# driverv7.net
KiCad netlist of a schematic drawn in Altium Designer
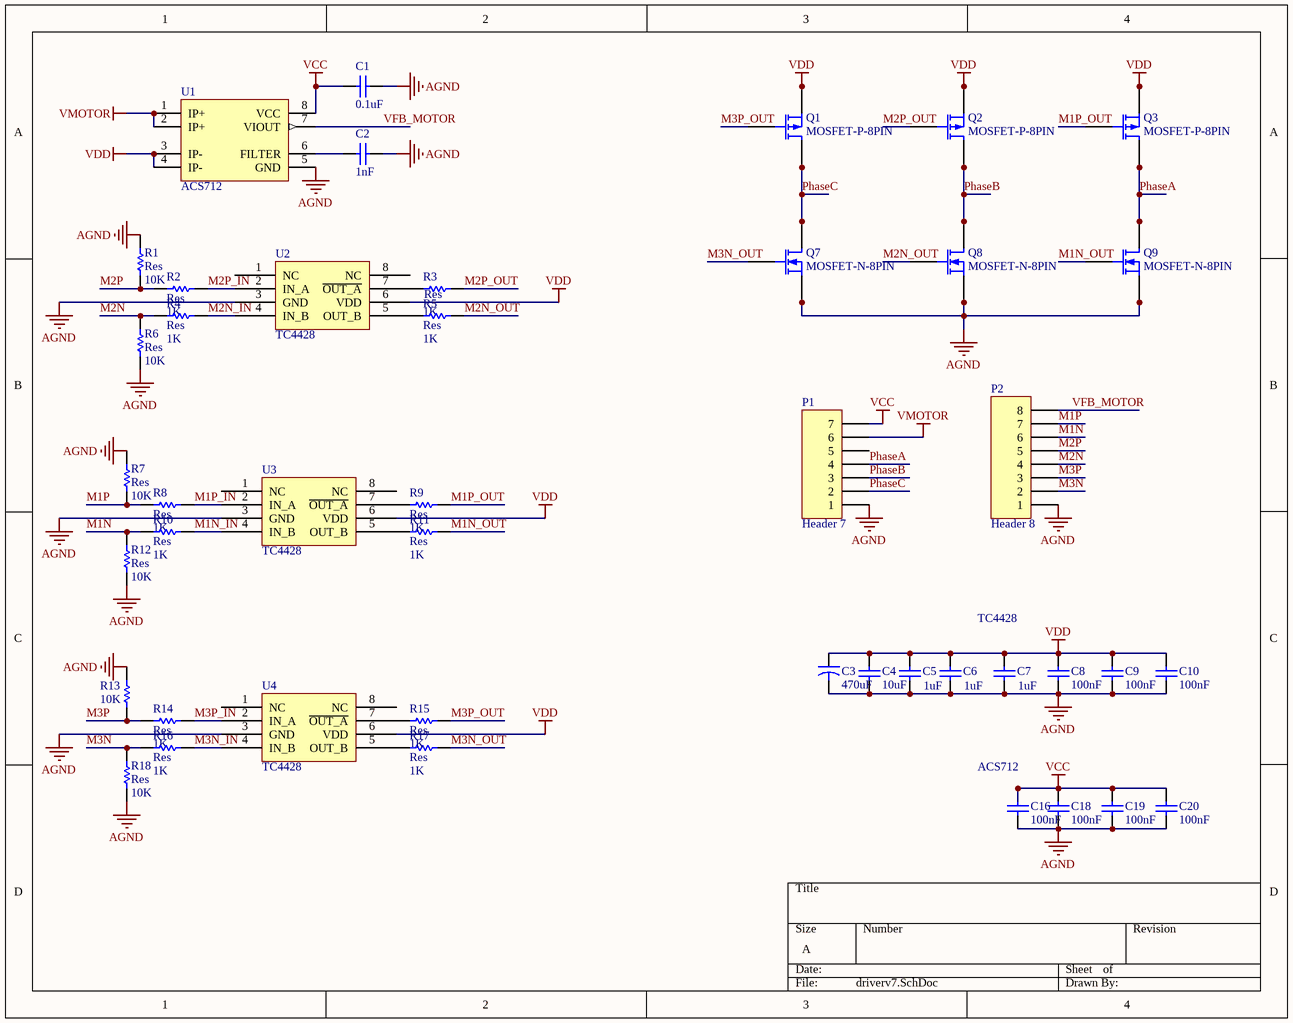
[diagram p0: driverv7.SchDoc]

(export (version "E")
  (design (tool "Eeschema 10.0.6"))
  (components
    (comp (ref "C1")
      (value "0.1uF")
      (footprint "2012[0805]")
      (description "Capacitor")
      (fields (field (name "Comment") "Cap_UP") (field (name "PUBLISHER") "Altium Limited"))
      (libsource (lib "KN2CLib") (part "Cap_UP"))
    )
    (comp (ref "C2")
      (value "1nF")
      (footprint "2012[0805]")
      (description "Capacitor")
      (fields (field (name "Comment") "Cap_UP") (field (name "PUBLISHER") "Altium Limited"))
      (libsource (lib "KN2CLib") (part "Cap_UP"))
    )
    (comp (ref "C3")
      (value "470uF")
      (footprint "7343")
      (description "Capacitor")
      (fields (field (name "Comment") "Cap_El_200V") (field (name "PUBLISHER") "Altium Limited"))
      (libsource (lib "KN2CLib") (part "Cap_El_200V"))
    )
    (comp (ref "C4")
      (value "10uF")
      (footprint "2012[0805]")
      (description "Capacitor")
      (fields (field (name "Comment") "Cap_UP") (field (name "PUBLISHER") "Altium Limited"))
      (libsource (lib "KN2CLib") (part "Cap_UP"))
    )
    (comp (ref "C5")
      (value "1uF")
      (footprint "2012[0805]")
      (description "Capacitor")
      (fields (field (name "Comment") "Cap_UP") (field (name "PUBLISHER") "Altium Limited"))
      (libsource (lib "KN2CLib") (part "Cap_UP"))
    )
    (comp (ref "C6")
      (value "1uF")
      (footprint "2012[0805]")
      (description "Capacitor")
      (fields (field (name "Comment") "Cap_UP") (field (name "PUBLISHER") "Altium Limited"))
      (libsource (lib "KN2CLib") (part "Cap_UP"))
    )
    (comp (ref "C7")
      (value "1uF")
      (footprint "2012[0805]")
      (description "Capacitor")
      (fields (field (name "Comment") "Cap_UP") (field (name "PUBLISHER") "Altium Limited"))
      (libsource (lib "KN2CLib") (part "Cap_UP"))
    )
    (comp (ref "C8")
      (value "100nF")
      (footprint "2012[0805]")
      (description "Capacitor")
      (fields (field (name "Comment") "Cap_UP") (field (name "PUBLISHER") "Altium Limited"))
      (libsource (lib "KN2CLib") (part "Cap_UP"))
    )
    (comp (ref "C9")
      (value "100nF")
      (footprint "2012[0805]")
      (description "Capacitor")
      (fields (field (name "Comment") "Cap_UP") (field (name "PUBLISHER") "Altium Limited"))
      (libsource (lib "KN2CLib") (part "Cap_UP"))
    )
    (comp (ref "C10")
      (value "100nF")
      (footprint "2012[0805]")
      (description "Capacitor")
      (fields (field (name "Comment") "Cap_UP") (field (name "PUBLISHER") "Altium Limited"))
      (libsource (lib "KN2CLib") (part "Cap_UP"))
    )
    (comp (ref "C16")
      (value "100nF")
      (footprint "2012[0805]")
      (description "Capacitor")
      (fields (field (name "Comment") "Cap_UP") (field (name "PUBLISHER") "Altium Limited"))
      (libsource (lib "KN2CLib") (part "Cap_UP"))
    )
    (comp (ref "C18")
      (value "100nF")
      (footprint "2012[0805]")
      (description "Capacitor")
      (fields (field (name "Comment") "Cap_UP") (field (name "PUBLISHER") "Altium Limited"))
      (libsource (lib "KN2CLib") (part "Cap_UP"))
    )
    (comp (ref "C19")
      (value "100nF")
      (footprint "2012[0805]")
      (description "Capacitor")
      (fields (field (name "Comment") "Cap_UP") (field (name "PUBLISHER") "Altium Limited"))
      (libsource (lib "KN2CLib") (part "Cap_UP"))
    )
    (comp (ref "C20")
      (value "100nF")
      (footprint "2012[0805]")
      (description "Capacitor")
      (fields (field (name "Comment") "Cap_UP") (field (name "PUBLISHER") "Altium Limited"))
      (libsource (lib "KN2CLib") (part "Cap_UP"))
    )
    (comp (ref "P1")
      (value "Header 7")
      (footprint "HDR1X7")
      (description "Header, 7-Pin")
      (fields (field (name "PUBLISHER") "Altium Limited"))
      (libsource (lib "Miscellaneous Connectors") (part "Header 7"))
    )
    (comp (ref "P2")
      (value "Header 8")
      (footprint "HDR1X8")
      (description "Header, 8-Pin")
      (fields (field (name "PUBLISHER") "Altium Limited"))
      (libsource (lib "Miscellaneous Connectors") (part "Header 8"))
    )
    (comp (ref "Q1")
      (value "MOSFET-P-8PIN")
      (footprint "SO-8_N")
      (description "P-Channel MOSFET")
      (fields (field (name "PUBLISHER") "Altium Limited"))
      (libsource (lib "KN2CLib") (part "MOSFET-P-8PIN"))
    )
    (comp (ref "Q2")
      (value "MOSFET-P-8PIN")
      (footprint "SO-8_N")
      (description "P-Channel MOSFET")
      (fields (field (name "PUBLISHER") "Altium Limited"))
      (libsource (lib "KN2CLib") (part "MOSFET-P-8PIN"))
    )
    (comp (ref "Q3")
      (value "MOSFET-P-8PIN")
      (footprint "SO-8_N")
      (description "P-Channel MOSFET")
      (fields (field (name "PUBLISHER") "Altium Limited"))
      (libsource (lib "KN2CLib") (part "MOSFET-P-8PIN"))
    )
    (comp (ref "Q7")
      (value "MOSFET-N-8PIN")
      (footprint "SO-8_N")
      (description "N-Channel MOSFET")
      (fields (field (name "PUBLISHER") "Altium Limited"))
      (libsource (lib "KN2CLib") (part "MOSFET-N-8PIN"))
    )
    (comp (ref "Q8")
      (value "MOSFET-N-8PIN")
      (footprint "SO-8_N")
      (description "N-Channel MOSFET")
      (fields (field (name "PUBLISHER") "Altium Limited"))
      (libsource (lib "KN2CLib") (part "MOSFET-N-8PIN"))
    )
    (comp (ref "Q9")
      (value "MOSFET-N-8PIN")
      (footprint "SO-8_N")
      (description "N-Channel MOSFET")
      (fields (field (name "PUBLISHER") "Altium Limited"))
      (libsource (lib "KN2CLib") (part "MOSFET-N-8PIN"))
    )
    (comp (ref "R1")
      (value "Res")
      (footprint "2012[0805]")
      (description "Semiconductor Resistor")
      (fields (field (name "ALTIUM_VALUE") "10K") (field (name "PUBLISHER") "Altium Limited"))
      (libsource (lib "KN2CLib") (part "Res"))
    )
    (comp (ref "R2")
      (value "Res")
      (footprint "2012[0805]")
      (description "Semiconductor Resistor")
      (fields (field (name "ALTIUM_VALUE") "1K") (field (name "PUBLISHER") "Altium Limited"))
      (libsource (lib "KN2CLib") (part "Res"))
    )
    (comp (ref "R3")
      (value "Res")
      (footprint "2012[0805]")
      (description "Semiconductor Resistor")
      (fields (field (name "ALTIUM_VALUE") "1K") (field (name "PUBLISHER") "Altium Limited"))
      (libsource (lib "KN2CLib") (part "Res"))
    )
    (comp (ref "R4")
      (value "Res")
      (footprint "2012[0805]")
      (description "Semiconductor Resistor")
      (fields (field (name "ALTIUM_VALUE") "1K") (field (name "PUBLISHER") "Altium Limited"))
      (libsource (lib "KN2CLib") (part "Res"))
    )
    (comp (ref "R5")
      (value "Res")
      (footprint "2012[0805]")
      (description "Semiconductor Resistor")
      (fields (field (name "ALTIUM_VALUE") "1K") (field (name "PUBLISHER") "Altium Limited"))
      (libsource (lib "KN2CLib") (part "Res"))
    )
    (comp (ref "R6")
      (value "Res")
      (footprint "2012[0805]")
      (description "Semiconductor Resistor")
      (fields (field (name "ALTIUM_VALUE") "10K") (field (name "PUBLISHER") "Altium Limited"))
      (libsource (lib "KN2CLib") (part "Res"))
    )
    (comp (ref "R7")
      (value "Res")
      (footprint "2012[0805]")
      (description "Semiconductor Resistor")
      (fields (field (name "ALTIUM_VALUE") "10K") (field (name "PUBLISHER") "Altium Limited"))
      (libsource (lib "KN2CLib") (part "Res"))
    )
    (comp (ref "R8")
      (value "Res")
      (footprint "2012[0805]")
      (description "Semiconductor Resistor")
      (fields (field (name "ALTIUM_VALUE") "1K") (field (name "PUBLISHER") "Altium Limited"))
      (libsource (lib "KN2CLib") (part "Res"))
    )
    (comp (ref "R9")
      (value "Res")
      (footprint "2012[0805]")
      (description "Semiconductor Resistor")
      (fields (field (name "ALTIUM_VALUE") "1K") (field (name "PUBLISHER") "Altium Limited"))
      (libsource (lib "KN2CLib") (part "Res"))
    )
    (comp (ref "R10")
      (value "Res")
      (footprint "2012[0805]")
      (description "Semiconductor Resistor")
      (fields (field (name "ALTIUM_VALUE") "1K") (field (name "PUBLISHER") "Altium Limited"))
      (libsource (lib "KN2CLib") (part "Res"))
    )
    (comp (ref "R11")
      (value "Res")
      (footprint "2012[0805]")
      (description "Semiconductor Resistor")
      (fields (field (name "ALTIUM_VALUE") "1K") (field (name "PUBLISHER") "Altium Limited"))
      (libsource (lib "KN2CLib") (part "Res"))
    )
    (comp (ref "R12")
      (value "Res")
      (footprint "2012[0805]")
      (description "Semiconductor Resistor")
      (fields (field (name "ALTIUM_VALUE") "10K") (field (name "PUBLISHER") "Altium Limited"))
      (libsource (lib "KN2CLib") (part "Res"))
    )
    (comp (ref "R13")
      (value "10K")
      (footprint "2012[0805]")
      (description "Semiconductor Resistor")
      (fields (field (name "Comment") "Res") (field (name "PUBLISHER") "Altium Limited"))
      (libsource (lib "KN2CLib") (part "Res"))
    )
    (comp (ref "R14")
      (value "Res")
      (footprint "2012[0805]")
      (description "Semiconductor Resistor")
      (fields (field (name "ALTIUM_VALUE") "1K") (field (name "PUBLISHER") "Altium Limited"))
      (libsource (lib "KN2CLib") (part "Res"))
    )
    (comp (ref "R15")
      (value "Res")
      (footprint "2012[0805]")
      (description "Semiconductor Resistor")
      (fields (field (name "ALTIUM_VALUE") "1K") (field (name "PUBLISHER") "Altium Limited"))
      (libsource (lib "KN2CLib") (part "Res"))
    )
    (comp (ref "R16")
      (value "Res")
      (footprint "2012[0805]")
      (description "Semiconductor Resistor")
      (fields (field (name "ALTIUM_VALUE") "1K") (field (name "PUBLISHER") "Altium Limited"))
      (libsource (lib "KN2CLib") (part "Res"))
    )
    (comp (ref "R17")
      (value "Res")
      (footprint "2012[0805]")
      (description "Semiconductor Resistor")
      (fields (field (name "ALTIUM_VALUE") "1K") (field (name "PUBLISHER") "Altium Limited"))
      (libsource (lib "KN2CLib") (part "Res"))
    )
    (comp (ref "R18")
      (value "Res")
      (footprint "2012[0805]")
      (description "Semiconductor Resistor")
      (fields (field (name "ALTIUM_VALUE") "10K") (field (name "PUBLISHER") "Altium Limited"))
      (libsource (lib "KN2CLib") (part "Res"))
    )
    (comp (ref "U1") (value "ACS712") (footprint "8 pin SOIC_N") (libsource (lib "KN2CLib") (part "ACS712")))
    (comp (ref "U2")
      (value "TC4428")
      (footprint "8 pin SOIC_M")
      (description "Dual MOSFET Driver")
      (libsource (lib "KN2CLib") (part "TC4428"))
    )
    (comp (ref "U3")
      (value "TC4428")
      (footprint "8 pin SOIC_M")
      (description "Dual MOSFET Driver")
      (libsource (lib "KN2CLib") (part "TC4428"))
    )
    (comp (ref "U4")
      (value "TC4428")
      (footprint "8 pin SOIC_M")
      (description "Dual MOSFET Driver")
      (libsource (lib "KN2CLib") (part "TC4428"))
    )
  )
  (nets
    (net (code "1") (name "/M1N") (class "Default")
      (node (ref "P2") (pin "6") (pinfunction "6_6") (pintype "passive"))
      (node (ref "R10") (pin "1") (pinfunction "1_1") (pintype "passive"))
      (node (ref "R12") (pin "2") (pinfunction "2_2") (pintype "passive"))
    )
    (net (code "2") (name "/M1N_IN") (class "Default")
      (node (ref "R10") (pin "2") (pinfunction "2_2") (pintype "passive"))
      (node (ref "U3") (pin "4") (pinfunction "IN_B_4") (pintype "passive"))
    )
    (net (code "3") (name "/M1N_OUT") (class "Default")
      (node (ref "Q9") (pin "4") (pinfunction "G_4") (pintype "passive"))
      (node (ref "R11") (pin "2") (pinfunction "2_2") (pintype "passive"))
    )
    (net (code "4") (name "/M1P") (class "Default")
      (node (ref "P2") (pin "7") (pinfunction "7_7") (pintype "passive"))
      (node (ref "R7") (pin "1") (pinfunction "1_1") (pintype "passive"))
      (node (ref "R8") (pin "1") (pinfunction "1_1") (pintype "passive"))
    )
    (net (code "5") (name "/M1P_IN") (class "Default")
      (node (ref "R8") (pin "2") (pinfunction "2_2") (pintype "passive"))
      (node (ref "U3") (pin "2") (pinfunction "IN_A_2") (pintype "passive"))
    )
    (net (code "6") (name "/M1P_OUT") (class "Default")
      (node (ref "Q3") (pin "4") (pinfunction "G_4") (pintype "passive"))
      (node (ref "R9") (pin "2") (pinfunction "2_2") (pintype "passive"))
    )
    (net (code "7") (name "/M2N") (class "Default")
      (node (ref "P2") (pin "4") (pinfunction "4_4") (pintype "passive"))
      (node (ref "R4") (pin "1") (pinfunction "1_1") (pintype "passive"))
      (node (ref "R6") (pin "2") (pinfunction "2_2") (pintype "passive"))
    )
    (net (code "8") (name "/M2N_IN") (class "Default")
      (node (ref "R4") (pin "2") (pinfunction "2_2") (pintype "passive"))
      (node (ref "U2") (pin "4") (pinfunction "IN_B_4") (pintype "passive"))
    )
    (net (code "9") (name "/M2N_OUT") (class "Default")
      (node (ref "Q8") (pin "4") (pinfunction "G_4") (pintype "passive"))
      (node (ref "R5") (pin "2") (pinfunction "2_2") (pintype "passive"))
    )
    (net (code "10") (name "/M2P") (class "Default")
      (node (ref "P2") (pin "5") (pinfunction "5_5") (pintype "passive"))
      (node (ref "R1") (pin "1") (pinfunction "1_1") (pintype "passive"))
      (node (ref "R2") (pin "1") (pinfunction "1_1") (pintype "passive"))
    )
    (net (code "11") (name "/M2P_IN") (class "Default")
      (node (ref "R2") (pin "2") (pinfunction "2_2") (pintype "passive"))
      (node (ref "U2") (pin "2") (pinfunction "IN_A_2") (pintype "passive"))
    )
    (net (code "12") (name "/M2P_OUT") (class "Default")
      (node (ref "Q2") (pin "4") (pinfunction "G_4") (pintype "passive"))
      (node (ref "R3") (pin "2") (pinfunction "2_2") (pintype "passive"))
    )
    (net (code "13") (name "/M3N") (class "Default")
      (node (ref "P2") (pin "2") (pinfunction "2_2") (pintype "passive"))
      (node (ref "R16") (pin "1") (pinfunction "1_1") (pintype "passive"))
      (node (ref "R18") (pin "2") (pinfunction "2_2") (pintype "passive"))
    )
    (net (code "14") (name "/M3N_IN") (class "Default")
      (node (ref "R16") (pin "2") (pinfunction "2_2") (pintype "passive"))
      (node (ref "U4") (pin "4") (pinfunction "IN_B_4") (pintype "passive"))
    )
    (net (code "15") (name "/M3N_OUT") (class "Default")
      (node (ref "Q7") (pin "4") (pinfunction "G_4") (pintype "passive"))
      (node (ref "R17") (pin "2") (pinfunction "2_2") (pintype "passive"))
    )
    (net (code "16") (name "/M3P") (class "Default")
      (node (ref "P2") (pin "3") (pinfunction "3_3") (pintype "passive"))
      (node (ref "R13") (pin "1") (pinfunction "1_1") (pintype "passive"))
      (node (ref "R14") (pin "1") (pinfunction "1_1") (pintype "passive"))
    )
    (net (code "17") (name "/M3P_IN") (class "Default")
      (node (ref "R14") (pin "2") (pinfunction "2_2") (pintype "passive"))
      (node (ref "U4") (pin "2") (pinfunction "IN_A_2") (pintype "passive"))
    )
    (net (code "18") (name "/M3P_OUT") (class "Default")
      (node (ref "Q1") (pin "4") (pinfunction "G_4") (pintype "passive"))
      (node (ref "R15") (pin "2") (pinfunction "2_2") (pintype "passive"))
    )
    (net (code "19") (name "/PhaseA") (class "Default")
      (node (ref "P1") (pin "4") (pinfunction "4_4") (pintype "passive"))
      (node (ref "Q3") (pin "5") (pinfunction "D_5") (pintype "passive"))
      (node (ref "Q3") (pin "6") (pinfunction "D_6") (pintype "passive"))
      (node (ref "Q3") (pin "7") (pinfunction "D_7") (pintype "passive"))
      (node (ref "Q3") (pin "8") (pinfunction "D_8") (pintype "passive"))
      (node (ref "Q9") (pin "5") (pinfunction "D_5") (pintype "passive"))
      (node (ref "Q9") (pin "6") (pinfunction "D_6") (pintype "passive"))
      (node (ref "Q9") (pin "7") (pinfunction "D_7") (pintype "passive"))
      (node (ref "Q9") (pin "8") (pinfunction "D_8") (pintype "passive"))
    )
    (net (code "20") (name "/PhaseB") (class "Default")
      (node (ref "P1") (pin "3") (pinfunction "3_3") (pintype "passive"))
      (node (ref "Q2") (pin "5") (pinfunction "D_5") (pintype "passive"))
      (node (ref "Q2") (pin "6") (pinfunction "D_6") (pintype "passive"))
      (node (ref "Q2") (pin "7") (pinfunction "D_7") (pintype "passive"))
      (node (ref "Q2") (pin "8") (pinfunction "D_8") (pintype "passive"))
      (node (ref "Q8") (pin "5") (pinfunction "D_5") (pintype "passive"))
      (node (ref "Q8") (pin "6") (pinfunction "D_6") (pintype "passive"))
      (node (ref "Q8") (pin "7") (pinfunction "D_7") (pintype "passive"))
      (node (ref "Q8") (pin "8") (pinfunction "D_8") (pintype "passive"))
    )
    (net (code "21") (name "/PhaseC") (class "Default")
      (node (ref "P1") (pin "2") (pinfunction "2_2") (pintype "passive"))
      (node (ref "Q1") (pin "5") (pinfunction "D_5") (pintype "passive"))
      (node (ref "Q1") (pin "6") (pinfunction "D_6") (pintype "passive"))
      (node (ref "Q1") (pin "7") (pinfunction "D_7") (pintype "passive"))
      (node (ref "Q1") (pin "8") (pinfunction "D_8") (pintype "passive"))
      (node (ref "Q7") (pin "5") (pinfunction "D_5") (pintype "passive"))
      (node (ref "Q7") (pin "6") (pinfunction "D_6") (pintype "passive"))
      (node (ref "Q7") (pin "7") (pinfunction "D_7") (pintype "passive"))
      (node (ref "Q7") (pin "8") (pinfunction "D_8") (pintype "passive"))
    )
    (net (code "22") (name "/VFB_MOTOR") (class "Default")
      (node (ref "P2") (pin "8") (pinfunction "8_8") (pintype "passive"))
      (node (ref "U1") (pin "7") (pinfunction "VIOUT_7") (pintype "output"))
    )
    (net (code "23") (name "AGND") (class "Default")
      (node (ref "C1") (pin "2") (pinfunction "2_2") (pintype "passive"))
      (node (ref "C10") (pin "1") (pinfunction "1_1") (pintype "passive"))
      (node (ref "C16") (pin "1") (pinfunction "1_1") (pintype "passive"))
      (node (ref "C18") (pin "1") (pinfunction "1_1") (pintype "passive"))
      (node (ref "C19") (pin "1") (pinfunction "1_1") (pintype "passive"))
      (node (ref "C2") (pin "2") (pinfunction "2_2") (pintype "passive"))
      (node (ref "C20") (pin "1") (pinfunction "1_1") (pintype "passive"))
      (node (ref "C3") (pin "2") (pinfunction "2_2") (pintype "passive"))
      (node (ref "C4") (pin "1") (pinfunction "1_1") (pintype "passive"))
      (node (ref "C5") (pin "1") (pinfunction "1_1") (pintype "passive"))
      (node (ref "C6") (pin "1") (pinfunction "1_1") (pintype "passive"))
      (node (ref "C7") (pin "1") (pinfunction "1_1") (pintype "passive"))
      (node (ref "C8") (pin "1") (pinfunction "1_1") (pintype "passive"))
      (node (ref "C9") (pin "1") (pinfunction "1_1") (pintype "passive"))
      (node (ref "P1") (pin "1") (pinfunction "1_1") (pintype "passive"))
      (node (ref "P2") (pin "1") (pinfunction "1_1") (pintype "passive"))
      (node (ref "Q7") (pin "1") (pinfunction "S_1") (pintype "passive"))
      (node (ref "Q7") (pin "2") (pinfunction "S_2") (pintype "passive"))
      (node (ref "Q7") (pin "3") (pinfunction "S_3") (pintype "passive"))
      (node (ref "Q8") (pin "1") (pinfunction "S_1") (pintype "passive"))
      (node (ref "Q8") (pin "2") (pinfunction "S_2") (pintype "passive"))
      (node (ref "Q8") (pin "3") (pinfunction "S_3") (pintype "passive"))
      (node (ref "Q9") (pin "1") (pinfunction "S_1") (pintype "passive"))
      (node (ref "Q9") (pin "2") (pinfunction "S_2") (pintype "passive"))
      (node (ref "Q9") (pin "3") (pinfunction "S_3") (pintype "passive"))
      (node (ref "R1") (pin "2") (pinfunction "2_2") (pintype "passive"))
      (node (ref "R12") (pin "1") (pinfunction "1_1") (pintype "passive"))
      (node (ref "R13") (pin "2") (pinfunction "2_2") (pintype "passive"))
      (node (ref "R18") (pin "1") (pinfunction "1_1") (pintype "passive"))
      (node (ref "R6") (pin "1") (pinfunction "1_1") (pintype "passive"))
      (node (ref "R7") (pin "2") (pinfunction "2_2") (pintype "passive"))
      (node (ref "U1") (pin "5") (pinfunction "GND_5") (pintype "power_in"))
      (node (ref "U2") (pin "3") (pinfunction "GND_3") (pintype "passive"))
      (node (ref "U3") (pin "3") (pinfunction "GND_3") (pintype "passive"))
      (node (ref "U4") (pin "3") (pinfunction "GND_3") (pintype "passive"))
    )
    (net (code "24") (name "Net-(U1-FILTER)") (class "Default")
      (node (ref "C2") (pin "1") (pinfunction "1_1") (pintype "passive"))
      (node (ref "U1") (pin "6") (pinfunction "FILTER_6") (pintype "passive"))
    )
    (net (code "25") (name "Net-(U2-OUT_B)") (class "Default")
      (node (ref "R5") (pin "1") (pinfunction "1_1") (pintype "passive"))
      (node (ref "U2") (pin "5") (pinfunction "OUT_B_5") (pintype "passive"))
    )
    (net (code "26") (name "Net-(U2-~{OUT_A})") (class "Default")
      (node (ref "R3") (pin "1") (pinfunction "1_1") (pintype "passive"))
      (node (ref "U2") (pin "7") (pinfunction "~{OUT_A}_7") (pintype "passive"))
    )
    (net (code "27") (name "Net-(U3-OUT_B)") (class "Default")
      (node (ref "R11") (pin "1") (pinfunction "1_1") (pintype "passive"))
      (node (ref "U3") (pin "5") (pinfunction "OUT_B_5") (pintype "passive"))
    )
    (net (code "28") (name "Net-(U3-~{OUT_A})") (class "Default")
      (node (ref "R9") (pin "1") (pinfunction "1_1") (pintype "passive"))
      (node (ref "U3") (pin "7") (pinfunction "~{OUT_A}_7") (pintype "passive"))
    )
    (net (code "29") (name "Net-(U4-OUT_B)") (class "Default")
      (node (ref "R17") (pin "1") (pinfunction "1_1") (pintype "passive"))
      (node (ref "U4") (pin "5") (pinfunction "OUT_B_5") (pintype "passive"))
    )
    (net (code "30") (name "Net-(U4-~{OUT_A})") (class "Default")
      (node (ref "R15") (pin "1") (pinfunction "1_1") (pintype "passive"))
      (node (ref "U4") (pin "7") (pinfunction "~{OUT_A}_7") (pintype "passive"))
    )
    (net (code "31") (name "VCC") (class "Default")
      (node (ref "C1") (pin "1") (pinfunction "1_1") (pintype "passive"))
      (node (ref "C16") (pin "2") (pinfunction "2_2") (pintype "passive"))
      (node (ref "C18") (pin "2") (pinfunction "2_2") (pintype "passive"))
      (node (ref "C19") (pin "2") (pinfunction "2_2") (pintype "passive"))
      (node (ref "C20") (pin "2") (pinfunction "2_2") (pintype "passive"))
      (node (ref "P1") (pin "7") (pinfunction "7_7") (pintype "passive"))
      (node (ref "U1") (pin "8") (pinfunction "VCC_8") (pintype "power_in"))
    )
    (net (code "32") (name "VDD") (class "Default")
      (node (ref "C10") (pin "2") (pinfunction "2_2") (pintype "passive"))
      (node (ref "C3") (pin "1") (pinfunction "1_1") (pintype "passive"))
      (node (ref "C4") (pin "2") (pinfunction "2_2") (pintype "passive"))
      (node (ref "C5") (pin "2") (pinfunction "2_2") (pintype "passive"))
      (node (ref "C6") (pin "2") (pinfunction "2_2") (pintype "passive"))
      (node (ref "C7") (pin "2") (pinfunction "2_2") (pintype "passive"))
      (node (ref "C8") (pin "2") (pinfunction "2_2") (pintype "passive"))
      (node (ref "C9") (pin "2") (pinfunction "2_2") (pintype "passive"))
      (node (ref "Q1") (pin "1") (pinfunction "S_1") (pintype "passive"))
      (node (ref "Q1") (pin "2") (pinfunction "S_2") (pintype "passive"))
      (node (ref "Q1") (pin "3") (pinfunction "S_3") (pintype "passive"))
      (node (ref "Q2") (pin "1") (pinfunction "S_1") (pintype "passive"))
      (node (ref "Q2") (pin "2") (pinfunction "S_2") (pintype "passive"))
      (node (ref "Q2") (pin "3") (pinfunction "S_3") (pintype "passive"))
      (node (ref "Q3") (pin "1") (pinfunction "S_1") (pintype "passive"))
      (node (ref "Q3") (pin "2") (pinfunction "S_2") (pintype "passive"))
      (node (ref "Q3") (pin "3") (pinfunction "S_3") (pintype "passive"))
      (node (ref "U1") (pin "3") (pinfunction "IP-_3") (pintype "passive"))
      (node (ref "U1") (pin "4") (pinfunction "IP-_4") (pintype "passive"))
      (node (ref "U2") (pin "6") (pinfunction "VDD_6") (pintype "passive"))
      (node (ref "U3") (pin "6") (pinfunction "VDD_6") (pintype "passive"))
      (node (ref "U4") (pin "6") (pinfunction "VDD_6") (pintype "passive"))
    )
    (net (code "33") (name "VMOTOR") (class "Default")
      (node (ref "P1") (pin "6") (pinfunction "6_6") (pintype "passive"))
      (node (ref "U1") (pin "1") (pinfunction "IP+_1") (pintype "passive"))
      (node (ref "U1") (pin "2") (pinfunction "IP+_2") (pintype "passive"))
    )
    (net (code "34") (name "unconnected-(P1-Pad5)") (class "Default")
      (node (ref "P1") (pin "5") (pinfunction "5_5") (pintype "passive"))
    )
    (net (code "35") (name "unconnected-(U2-NC-Pad1)") (class "Default")
      (node (ref "U2") (pin "1") (pinfunction "NC_1") (pintype "passive"))
    )
    (net (code "36") (name "unconnected-(U2-NC-Pad8)") (class "Default")
      (node (ref "U2") (pin "8") (pinfunction "NC_8") (pintype "passive"))
    )
    (net (code "37") (name "unconnected-(U3-NC-Pad1)") (class "Default")
      (node (ref "U3") (pin "1") (pinfunction "NC_1") (pintype "passive"))
    )
    (net (code "38") (name "unconnected-(U3-NC-Pad8)") (class "Default")
      (node (ref "U3") (pin "8") (pinfunction "NC_8") (pintype "passive"))
    )
    (net (code "39") (name "unconnected-(U4-NC-Pad1)") (class "Default")
      (node (ref "U4") (pin "1") (pinfunction "NC_1") (pintype "passive"))
    )
    (net (code "40") (name "unconnected-(U4-NC-Pad8)") (class "Default")
      (node (ref "U4") (pin "8") (pinfunction "NC_8") (pintype "passive"))
    )
  )
)
